# neo.net
KiCad netlist of a schematic drawn in EAGLE
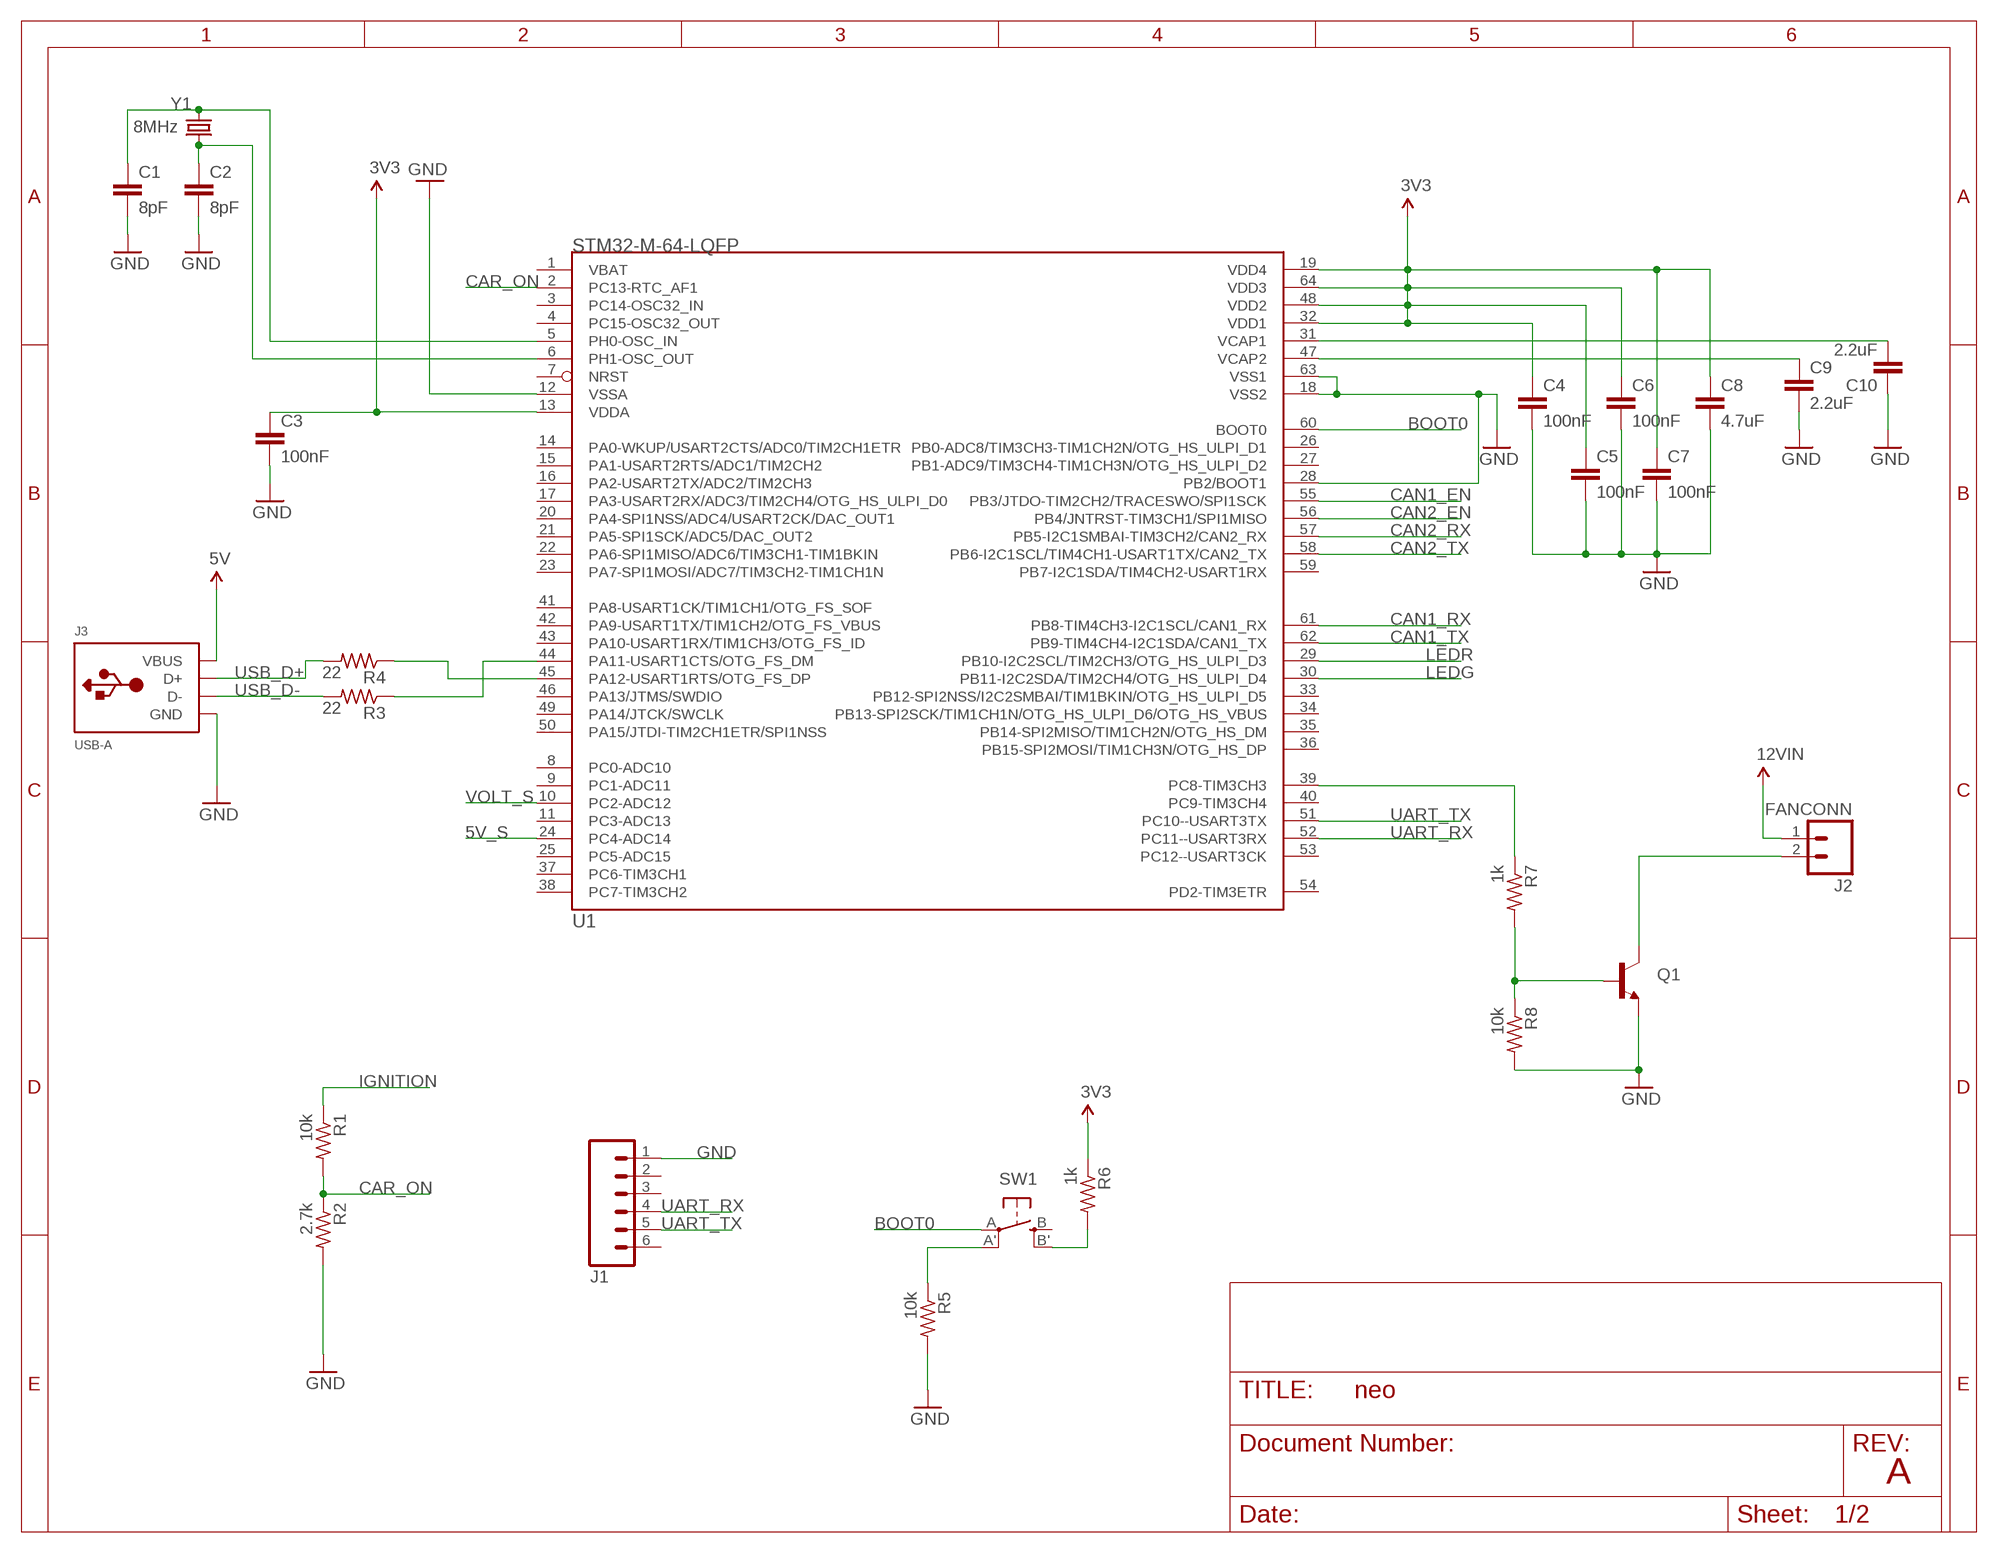
[diagram p0: schematic, sheet 1]
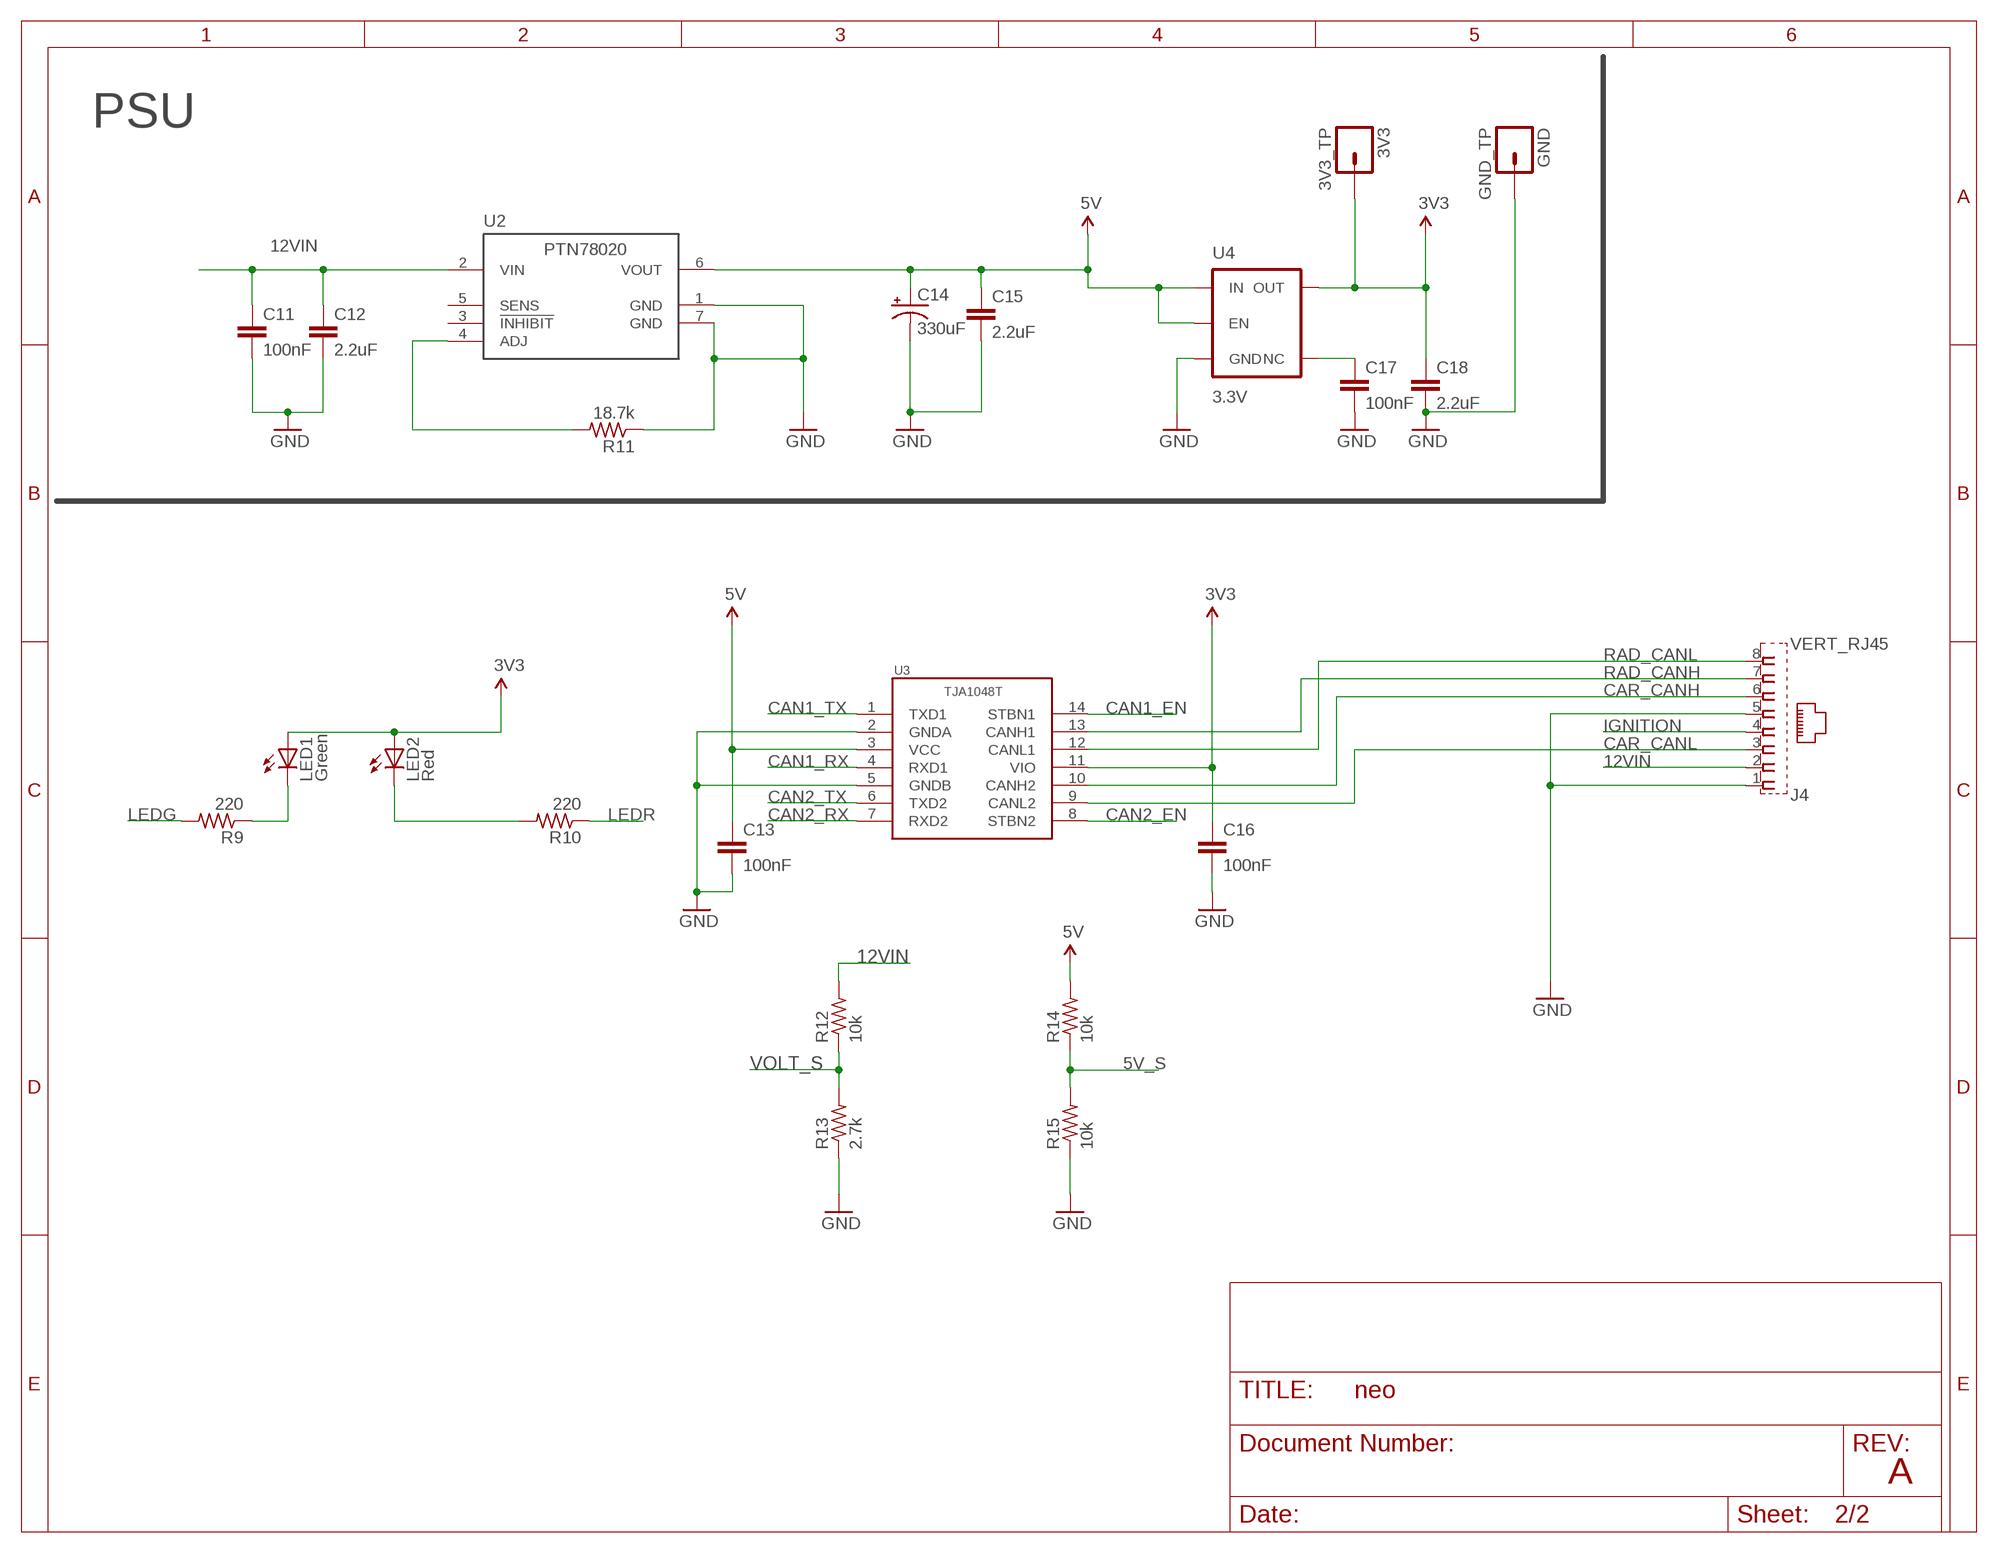
[diagram p1: schematic, sheet 2]

(export (version "E")
  (design (tool "Eeschema 10.0.6"))
  (components
    (comp (ref "C1")
      (value "8pF")
      (footprint "eagle-import:0603-CAP")
      (libsource (lib "eagle-import") (part "1.0UF-16V-10%(0603)"))
    )
    (comp (ref "C2")
      (value "8pF")
      (footprint "eagle-import:0603-CAP")
      (libsource (lib "eagle-import") (part "1.0UF-16V-10%(0603)"))
    )
    (comp (ref "C3")
      (value "100nF")
      (footprint "eagle-import:0603-CAP")
      (libsource (lib "eagle-import") (part "1.0UF-16V-10%(0603)"))
    )
    (comp (ref "C4")
      (value "100nF")
      (footprint "eagle-import:0603-CAP")
      (libsource (lib "eagle-import") (part "1.0UF-16V-10%(0603)"))
    )
    (comp (ref "C5")
      (value "100nF")
      (footprint "eagle-import:0603-CAP")
      (libsource (lib "eagle-import") (part "1.0UF-16V-10%(0603)"))
    )
    (comp (ref "C6")
      (value "100nF")
      (footprint "eagle-import:0603-CAP")
      (libsource (lib "eagle-import") (part "0.1UF-25V-5%(0603)"))
    )
    (comp (ref "C7")
      (value "100nF")
      (footprint "eagle-import:0603-CAP")
      (libsource (lib "eagle-import") (part "1.0UF-16V-10%(0603)"))
    )
    (comp (ref "C8")
      (value "4.7uF")
      (footprint "eagle-import:0603-CAP")
      (libsource (lib "eagle-import") (part "1.0UF-16V-10%(0603)"))
    )
    (comp (ref "C9")
      (value "2.2uF")
      (footprint "eagle-import:0603-CAP")
      (libsource (lib "eagle-import") (part "1.0UF-16V-10%(0603)"))
    )
    (comp (ref "C10")
      (value "2.2uF")
      (footprint "eagle-import:0603-CAP")
      (libsource (lib "eagle-import") (part "1.0UF-16V-10%(0603)"))
    )
    (comp (ref "J1")
      (value "M06NO_SILK_YES_STOP")
      (footprint "eagle-import:1X06_NO_SILK_YES_STOP")
      (libsource (lib "eagle-import") (part "M06NO_SILK_YES_STOP"))
    )
    (comp (ref "J2")
      (value "FANCONN")
      (footprint "eagle-import:1.25CONN")
      (libsource (lib "eagle-import") (part "FANCONN"))
    )
    (comp (ref "J3")
      (value "USB-A")
      (footprint "eagle-import:MOLEX_480371000")
      (libsource (lib "eagle-import") (part "USB-A"))
    )
    (comp (ref "Q1")
      (value "MMBT2222A")
      (footprint "eagle-import:SOT23-3")
      (libsource (lib "eagle-import") (part "TRANSISTOR_NPNMMBT2222A"))
    )
    (comp (ref "R1")
      (value "10k")
      (footprint "eagle-import:R0603")
      (libsource (lib "eagle-import") (part "R-US_R0603"))
    )
    (comp (ref "R2")
      (value "2.7k")
      (footprint "eagle-import:R0603")
      (libsource (lib "eagle-import") (part "R-US_R0603"))
    )
    (comp (ref "R3")
      (value "22")
      (footprint "eagle-import:R0603")
      (libsource (lib "eagle-import") (part "R-US_R0603"))
    )
    (comp (ref "R4")
      (value "22")
      (footprint "eagle-import:R0603")
      (libsource (lib "eagle-import") (part "R-US_R0603"))
    )
    (comp (ref "R5")
      (value "10k")
      (footprint "eagle-import:R0603")
      (libsource (lib "eagle-import") (part "R-US_R0603"))
    )
    (comp (ref "R6")
      (value "1k")
      (footprint "eagle-import:R0603")
      (libsource (lib "eagle-import") (part "R-US_R0603"))
    )
    (comp (ref "R7")
      (value "1k")
      (footprint "eagle-import:R0603")
      (libsource (lib "eagle-import") (part "R-US_R0603"))
    )
    (comp (ref "R8")
      (value "10k")
      (footprint "eagle-import:R0603")
      (libsource (lib "eagle-import") (part "R-US_R0603"))
    )
    (comp (ref "SW1")
      (value "SPST_TACT-EVQQ2")
      (footprint "eagle-import:EVQ-Q2")
      (libsource (lib "eagle-import") (part "SPST_TACT-EVQQ2"))
    )
    (comp (ref "U1")
      (value "STM32-M-64-LQFP")
      (footprint "eagle-import:LQFP64")
      (libsource (lib "eagle-import") (part "STM32-M-64-LQFP"))
    )
    (comp (ref "Y1")
      (value "8MHz")
      (footprint "eagle-import:CRYSTAL-TXC-7A")
      (libsource (lib "eagle-import") (part "CRYSTALTXC-7A"))
    )
    (comp (ref "3V3")
      (value "3V3_TP")
      (footprint "eagle-import:1X01_NO_SILK")
      (libsource (lib "eagle-import") (part "M01PTH_NO_SILK_YES_STOP"))
    )
    (comp (ref "C11")
      (value "100nF")
      (footprint "eagle-import:0603-CAP")
      (libsource (lib "eagle-import") (part "0.22UF-25V-10%(0603)"))
    )
    (comp (ref "C12")
      (value "2.2uF")
      (footprint "eagle-import:0805-CAP")
      (libsource (lib "eagle-import") (part "2.2UF-25V-+80/-20(0805)"))
    )
    (comp (ref "C13")
      (value "100nF")
      (footprint "eagle-import:0603-CAP")
      (libsource (lib "eagle-import") (part "CAP0603-CAP"))
    )
    (comp (ref "C14")
      (value "330uF")
      (footprint "eagle-import:E3,5-8")
      (libsource (lib "eagle-import") (part "C-POL"))
    )
    (comp (ref "C15")
      (value "2.2uF")
      (footprint "eagle-import:0805-CAP")
      (libsource (lib "eagle-import") (part "2.2UF-25V-+80/-20(0805)"))
    )
    (comp (ref "C16")
      (value "100nF")
      (footprint "eagle-import:0603-CAP")
      (libsource (lib "eagle-import") (part "CAP0603-CAP"))
    )
    (comp (ref "C17")
      (value "100nF")
      (footprint "eagle-import:0603-CAP")
      (libsource (lib "eagle-import") (part "CAP0603-CAP"))
    )
    (comp (ref "C18")
      (value "2.2uF")
      (footprint "eagle-import:0603-CAP")
      (libsource (lib "eagle-import") (part "CAP0603-CAP"))
    )
    (comp (ref "GND")
      (value "GND_TP")
      (footprint "eagle-import:1X01_NO_SILK")
      (libsource (lib "eagle-import") (part "M01PTH_NO_SILK_YES_STOP"))
    )
    (comp (ref "J4")
      (value "VERT_RJ45")
      (footprint "eagle-import:GLX-S-88M")
      (libsource (lib "eagle-import") (part "VERT_RJ45"))
    )
    (comp (ref "LED1")
      (value "Green")
      (footprint "eagle-import:CHIPLED_0805")
      (libsource (lib "eagle-import") (part "LEDCHIPLED_0805"))
    )
    (comp (ref "LED2")
      (value "Red")
      (footprint "eagle-import:CHIPLED_0805")
      (libsource (lib "eagle-import") (part "LEDCHIPLED_0805"))
    )
    (comp (ref "R9")
      (value "220")
      (footprint "eagle-import:R0603")
      (libsource (lib "eagle-import") (part "R-US_R0603"))
    )
    (comp (ref "R10")
      (value "220")
      (footprint "eagle-import:R0603")
      (libsource (lib "eagle-import") (part "R-US_R0603"))
    )
    (comp (ref "R11")
      (value "18.7k")
      (footprint "eagle-import:R0603")
      (libsource (lib "eagle-import") (part "R-US_R0603"))
    )
    (comp (ref "R12")
      (value "10k")
      (footprint "eagle-import:R0603")
      (libsource (lib "eagle-import") (part "R-US_R0603"))
    )
    (comp (ref "R13")
      (value "2.7k")
      (footprint "eagle-import:R0603")
      (libsource (lib "eagle-import") (part "R-US_R0603"))
    )
    (comp (ref "R14")
      (value "10k")
      (footprint "eagle-import:R0603")
      (libsource (lib "eagle-import") (part "R-US_R0603"))
    )
    (comp (ref "R15")
      (value "10k")
      (footprint "eagle-import:R0603")
      (libsource (lib "eagle-import") (part "R-US_R0603"))
    )
    (comp (ref "U2")
      (value "PTN78020W")
      (footprint "eagle-import:PTN78020W")
      (libsource (lib "eagle-import") (part "PTN78020W"))
    )
    (comp (ref "U3")
      (value "TJA1048")
      (footprint "eagle-import:SO14")
      (libsource (lib "eagle-import") (part "TJA1048"))
    )
    (comp (ref "U4")
      (value "3.3V")
      (footprint "eagle-import:SOT23-5")
      (libsource (lib "eagle-import") (part "V_REG_AP2112K-3.3V"))
    )
  )
  (nets
    (net (code "1") (name "3V3") (class "Default")
      (node (ref "3V3") (pin "1") (pinfunction "1_1") (pintype "passive"))
      (node (ref "C16") (pin "1") (pinfunction "1_1") (pintype "passive"))
      (node (ref "C18") (pin "1") (pinfunction "1_1") (pintype "passive"))
      (node (ref "C3") (pin "1") (pinfunction "1_1") (pintype "passive"))
      (node (ref "C4") (pin "1") (pinfunction "1_1") (pintype "passive"))
      (node (ref "C5") (pin "1") (pinfunction "1_1") (pintype "passive"))
      (node (ref "C6") (pin "1") (pinfunction "1_1") (pintype "passive"))
      (node (ref "C7") (pin "1") (pinfunction "1_1") (pintype "passive"))
      (node (ref "C8") (pin "1") (pinfunction "1_1") (pintype "passive"))
      (node (ref "LED1") (pin "A") (pinfunction "A_A") (pintype "passive"))
      (node (ref "LED2") (pin "A") (pinfunction "A_A") (pintype "passive"))
      (node (ref "R6") (pin "1") (pinfunction "1_1") (pintype "passive"))
      (node (ref "U1") (pin "13") (pinfunction "VDDA_13") (pintype "power_in"))
      (node (ref "U1") (pin "19") (pinfunction "VDD4_19") (pintype "bidirectional"))
      (node (ref "U1") (pin "32") (pinfunction "VDD1_32") (pintype "power_in"))
      (node (ref "U1") (pin "48") (pinfunction "VDD2_48") (pintype "power_in"))
      (node (ref "U1") (pin "64") (pinfunction "VDD3_64") (pintype "power_in"))
      (node (ref "U3") (pin "11") (pinfunction "VIO_11") (pintype "bidirectional"))
      (node (ref "U4") (pin "5") (pinfunction "OUT_5") (pintype "passive"))
    )
    (net (code "2") (name "5V") (class "Default")
      (node (ref "C13") (pin "1") (pinfunction "1_1") (pintype "passive"))
      (node (ref "C14") (pin "+") (pinfunction "+_+") (pintype "passive"))
      (node (ref "C15") (pin "1") (pinfunction "1_1") (pintype "passive"))
      (node (ref "J3") (pin "1") (pinfunction "VBUS_1") (pintype "power_in"))
      (node (ref "R14") (pin "2") (pinfunction "2_2") (pintype "passive"))
      (node (ref "U2") (pin "6") (pinfunction "VOUT_6") (pintype "bidirectional"))
      (node (ref "U3") (pin "3") (pinfunction "VCC_3") (pintype "power_in"))
      (node (ref "U4") (pin "1") (pinfunction "IN_1") (pintype "input"))
      (node (ref "U4") (pin "3") (pinfunction "EN_3") (pintype "input"))
    )
    (net (code "3") (name "5V_S") (class "Default")
      (node (ref "R14") (pin "1") (pinfunction "1_1") (pintype "passive"))
      (node (ref "R15") (pin "2") (pinfunction "2_2") (pintype "passive"))
      (node (ref "U1") (pin "24") (pinfunction "PC4-ADC14_24") (pintype "bidirectional"))
    )
    (net (code "4") (name "12VIN") (class "Default")
      (node (ref "C11") (pin "1") (pinfunction "1_1") (pintype "passive"))
      (node (ref "C12") (pin "1") (pinfunction "1_1") (pintype "passive"))
      (node (ref "J2") (pin "1") (pinfunction "1_1") (pintype "passive"))
      (node (ref "J4") (pin "2") (pinfunction "2_2") (pintype "passive"))
      (node (ref "R12") (pin "2") (pinfunction "2_2") (pintype "passive"))
      (node (ref "U2") (pin "2") (pinfunction "VIN_2") (pintype "bidirectional"))
    )
    (net (code "5") (name "BOOT0") (class "Default")
      (node (ref "SW1") (pin "A") (pinfunction "P_A") (pintype "passive"))
      (node (ref "U1") (pin "60") (pinfunction "BOOT0_60") (pintype "input"))
    )
    (net (code "6") (name "CAN1_EN") (class "Default")
      (node (ref "U1") (pin "55") (pinfunction "PB3/JTDO-TIM2CH2/TRACESWO/SPI1SCK_55") (pintype "bidirectional"))
      (node (ref "U3") (pin "14") (pinfunction "STBN1_14") (pintype "bidirectional"))
    )
    (net (code "7") (name "CAN1_RX") (class "Default")
      (node (ref "U1") (pin "61") (pinfunction "PB8-TIM4CH3-I2C1SCL/CAN1_RX_61") (pintype "bidirectional"))
      (node (ref "U3") (pin "4") (pinfunction "RXD1_4") (pintype "bidirectional"))
    )
    (net (code "8") (name "CAN1_TX") (class "Default")
      (node (ref "U1") (pin "62") (pinfunction "PB9-TIM4CH4-I2C1SDA/CAN1_TX_62") (pintype "bidirectional"))
      (node (ref "U3") (pin "1") (pinfunction "TXD1_1") (pintype "bidirectional"))
    )
    (net (code "9") (name "CAN2_EN") (class "Default")
      (node (ref "U1") (pin "56") (pinfunction "PB4/JNTRST-TIM3CH1/SPI1MISO_56") (pintype "bidirectional"))
      (node (ref "U3") (pin "8") (pinfunction "STBN2_8") (pintype "bidirectional"))
    )
    (net (code "10") (name "CAN2_RX") (class "Default")
      (node (ref "U1") (pin "57") (pinfunction "PB5-I2C1SMBAI-TIM3CH2/CAN2_RX_57") (pintype "bidirectional"))
      (node (ref "U3") (pin "7") (pinfunction "RXD2_7") (pintype "bidirectional"))
    )
    (net (code "11") (name "CAN2_TX") (class "Default")
      (node (ref "U1") (pin "58") (pinfunction "PB6-I2C1SCL/TIM4CH1-USART1TX/CAN2_TX_58") (pintype "bidirectional"))
      (node (ref "U3") (pin "6") (pinfunction "TXD2_6") (pintype "bidirectional"))
    )
    (net (code "12") (name "CAR_CANH") (class "Default")
      (node (ref "J4") (pin "6") (pinfunction "6_6") (pintype "passive"))
      (node (ref "U3") (pin "10") (pinfunction "CANH2_10") (pintype "bidirectional"))
    )
    (net (code "13") (name "CAR_CANL") (class "Default")
      (node (ref "J4") (pin "3") (pinfunction "3_3") (pintype "passive"))
      (node (ref "U3") (pin "9") (pinfunction "CANL2_9") (pintype "bidirectional"))
    )
    (net (code "14") (name "CAR_ON") (class "Default")
      (node (ref "R1") (pin "2") (pinfunction "2_2") (pintype "passive"))
      (node (ref "R2") (pin "1") (pinfunction "1_1") (pintype "passive"))
      (node (ref "U1") (pin "2") (pinfunction "PC13-RTC_AF1_2") (pintype "bidirectional"))
    )
    (net (code "15") (name "GND") (class "Default")
      (node (ref "C1") (pin "2") (pinfunction "2_2") (pintype "passive"))
      (node (ref "C10") (pin "1") (pinfunction "1_1") (pintype "passive"))
      (node (ref "C11") (pin "2") (pinfunction "2_2") (pintype "passive"))
      (node (ref "C12") (pin "2") (pinfunction "2_2") (pintype "passive"))
      (node (ref "C13") (pin "2") (pinfunction "2_2") (pintype "passive"))
      (node (ref "C14") (pin "-") (pinfunction "-_-") (pintype "passive"))
      (node (ref "C15") (pin "2") (pinfunction "2_2") (pintype "passive"))
      (node (ref "C16") (pin "2") (pinfunction "2_2") (pintype "passive"))
      (node (ref "C17") (pin "2") (pinfunction "2_2") (pintype "passive"))
      (node (ref "C18") (pin "2") (pinfunction "2_2") (pintype "passive"))
      (node (ref "C2") (pin "2") (pinfunction "2_2") (pintype "passive"))
      (node (ref "C3") (pin "2") (pinfunction "2_2") (pintype "passive"))
      (node (ref "C4") (pin "2") (pinfunction "2_2") (pintype "passive"))
      (node (ref "C5") (pin "2") (pinfunction "2_2") (pintype "passive"))
      (node (ref "C6") (pin "2") (pinfunction "2_2") (pintype "passive"))
      (node (ref "C7") (pin "2") (pinfunction "2_2") (pintype "passive"))
      (node (ref "C8") (pin "2") (pinfunction "2_2") (pintype "passive"))
      (node (ref "C9") (pin "2") (pinfunction "2_2") (pintype "passive"))
      (node (ref "GND") (pin "1") (pinfunction "1_1") (pintype "passive"))
      (node (ref "J1") (pin "1") (pinfunction "1_1") (pintype "passive"))
      (node (ref "J3") (pin "4") (pinfunction "GND_4") (pintype "power_in"))
      (node (ref "J4") (pin "1") (pinfunction "1_1") (pintype "passive"))
      (node (ref "J4") (pin "5") (pinfunction "5_5") (pintype "passive"))
      (node (ref "Q1") (pin "2") (pinfunction "E_2") (pintype "passive"))
      (node (ref "R11") (pin "1") (pinfunction "1_1") (pintype "passive"))
      (node (ref "R13") (pin "1") (pinfunction "1_1") (pintype "passive"))
      (node (ref "R15") (pin "1") (pinfunction "1_1") (pintype "passive"))
      (node (ref "R2") (pin "2") (pinfunction "2_2") (pintype "passive"))
      (node (ref "R5") (pin "2") (pinfunction "2_2") (pintype "passive"))
      (node (ref "R8") (pin "2") (pinfunction "2_2") (pintype "passive"))
      (node (ref "U1") (pin "12") (pinfunction "VSSA_12") (pintype "power_in"))
      (node (ref "U1") (pin "18") (pinfunction "VSS2_18") (pintype "bidirectional"))
      (node (ref "U1") (pin "28") (pinfunction "PB2/BOOT1_28") (pintype "bidirectional"))
      (node (ref "U1") (pin "63") (pinfunction "VSS1_63") (pintype "power_in"))
      (node (ref "U2") (pin "1") (pinfunction "GND_1") (pintype "bidirectional"))
      (node (ref "U2") (pin "7") (pinfunction "GND_7") (pintype "bidirectional"))
      (node (ref "U3") (pin "2") (pinfunction "GNDA_2") (pintype "bidirectional"))
      (node (ref "U3") (pin "5") (pinfunction "GNDB_5") (pintype "bidirectional"))
      (node (ref "U4") (pin "2") (pinfunction "GND_2") (pintype "input"))
    )
    (net (code "16") (name "IGNITION") (class "Default")
      (node (ref "J4") (pin "4") (pinfunction "4_4") (pintype "passive"))
      (node (ref "R1") (pin "1") (pinfunction "1_1") (pintype "passive"))
    )
    (net (code "17") (name "LEDG") (class "Default")
      (node (ref "R9") (pin "2") (pinfunction "2_2") (pintype "passive"))
      (node (ref "U1") (pin "30") (pinfunction "PB11-I2C2SDA/TIM2CH4/OTG_HS_ULPI_D4_30") (pintype "bidirectional"))
    )
    (net (code "18") (name "LEDR") (class "Default")
      (node (ref "R10") (pin "1") (pinfunction "1_1") (pintype "passive"))
      (node (ref "U1") (pin "29") (pinfunction "PB10-I2C2SCL/TIM2CH3/OTG_HS_ULPI_D3_29") (pintype "bidirectional"))
    )
    (net (code "19") (name "Net-(LED1-PadC)") (class "Default")
      (node (ref "LED1") (pin "C") (pinfunction "C_C") (pintype "passive"))
      (node (ref "R9") (pin "1") (pinfunction "1_1") (pintype "passive"))
    )
    (net (code "20") (name "Net-(LED2-PadC)") (class "Default")
      (node (ref "LED2") (pin "C") (pinfunction "C_C") (pintype "passive"))
      (node (ref "R10") (pin "2") (pinfunction "2_2") (pintype "passive"))
    )
    (net (code "21") (name "Net-(Q1-B)") (class "Default")
      (node (ref "Q1") (pin "1") (pinfunction "B_1") (pintype "passive"))
      (node (ref "R7") (pin "2") (pinfunction "2_2") (pintype "passive"))
      (node (ref "R8") (pin "1") (pinfunction "1_1") (pintype "passive"))
    )
    (net (code "22") (name "Net-(Q1-C)") (class "Default")
      (node (ref "J2") (pin "2") (pinfunction "2_2") (pintype "passive"))
      (node (ref "Q1") (pin "3") (pinfunction "C_3") (pintype "passive"))
    )
    (net (code "23") (name "Net-(SW1-P1)") (class "Default")
      (node (ref "R5") (pin "1") (pinfunction "1_1") (pintype "passive"))
      (node (ref "SW1") (pin "A'") (pinfunction "P1_A'") (pintype "passive"))
    )
    (net (code "24") (name "Net-(SW1-S1)") (class "Default")
      (node (ref "R6") (pin "2") (pinfunction "2_2") (pintype "passive"))
      (node (ref "SW1") (pin "B'") (pinfunction "S1_B'") (pintype "passive"))
    )
    (net (code "25") (name "Net-(U1-PA11-USART1CTS{slash}OTG_FS_DM)") (class "Default")
      (node (ref "R3") (pin "1") (pinfunction "1_1") (pintype "passive"))
      (node (ref "U1") (pin "44") (pinfunction "PA11-USART1CTS/OTG_FS_DM_44") (pintype "bidirectional"))
    )
    (net (code "26") (name "Net-(U1-PA12-USART1RTS{slash}OTG_FS_DP)") (class "Default")
      (node (ref "R4") (pin "1") (pinfunction "1_1") (pintype "passive"))
      (node (ref "U1") (pin "45") (pinfunction "PA12-USART1RTS/OTG_FS_DP_45") (pintype "bidirectional"))
    )
    (net (code "27") (name "Net-(U1-PC8-TIM3CH3)") (class "Default")
      (node (ref "R7") (pin "1") (pinfunction "1_1") (pintype "passive"))
      (node (ref "U1") (pin "39") (pinfunction "PC8-TIM3CH3_39") (pintype "bidirectional"))
    )
    (net (code "28") (name "Net-(U1-PH0-OSC_IN)") (class "Default")
      (node (ref "C1") (pin "1") (pinfunction "1_1") (pintype "passive"))
      (node (ref "U1") (pin "5") (pinfunction "PH0-OSC_IN_5") (pintype "input"))
      (node (ref "Y1") (pin "P$1") (pinfunction "1_P$1") (pintype "passive"))
    )
    (net (code "29") (name "Net-(U1-PH1-OSC_OUT)") (class "Default")
      (node (ref "C2") (pin "1") (pinfunction "1_1") (pintype "passive"))
      (node (ref "U1") (pin "6") (pinfunction "PH1-OSC_OUT_6") (pintype "output"))
      (node (ref "Y1") (pin "P$2") (pinfunction "2_P$2") (pintype "passive"))
    )
    (net (code "30") (name "Net-(U1-VCAP1)") (class "Default")
      (node (ref "C10") (pin "2") (pinfunction "2_2") (pintype "passive"))
      (node (ref "U1") (pin "31") (pinfunction "VCAP1_31") (pintype "power_in"))
    )
    (net (code "31") (name "Net-(U1-VCAP2)") (class "Default")
      (node (ref "C9") (pin "1") (pinfunction "1_1") (pintype "passive"))
      (node (ref "U1") (pin "47") (pinfunction "VCAP2_47") (pintype "power_in"))
    )
    (net (code "32") (name "Net-(U2-ADJ)") (class "Default")
      (node (ref "R11") (pin "2") (pinfunction "2_2") (pintype "passive"))
      (node (ref "U2") (pin "4") (pinfunction "ADJ_4") (pintype "bidirectional"))
    )
    (net (code "33") (name "Net-(U4-NC)") (class "Default")
      (node (ref "C17") (pin "1") (pinfunction "1_1") (pintype "passive"))
      (node (ref "U4") (pin "4") (pinfunction "NC_4") (pintype "input"))
    )
    (net (code "34") (name "RAD_CANH") (class "Default")
      (node (ref "J4") (pin "7") (pinfunction "7_7") (pintype "passive"))
      (node (ref "U3") (pin "13") (pinfunction "CANH1_13") (pintype "bidirectional"))
    )
    (net (code "35") (name "RAD_CANL") (class "Default")
      (node (ref "J4") (pin "8") (pinfunction "8_8") (pintype "passive"))
      (node (ref "U3") (pin "12") (pinfunction "CANL1_12") (pintype "bidirectional"))
    )
    (net (code "36") (name "UART_RX") (class "Default")
      (node (ref "J1") (pin "4") (pinfunction "4_4") (pintype "passive"))
      (node (ref "U1") (pin "52") (pinfunction "PC11--USART3RX_52") (pintype "bidirectional"))
    )
    (net (code "37") (name "UART_TX") (class "Default")
      (node (ref "J1") (pin "5") (pinfunction "5_5") (pintype "passive"))
      (node (ref "U1") (pin "51") (pinfunction "PC10--USART3TX_51") (pintype "bidirectional"))
    )
    (net (code "38") (name "USB_D+") (class "Default")
      (node (ref "J3") (pin "3") (pinfunction "D+_3") (pintype "bidirectional"))
      (node (ref "R4") (pin "2") (pinfunction "2_2") (pintype "passive"))
    )
    (net (code "39") (name "USB_D-") (class "Default")
      (node (ref "J3") (pin "2") (pinfunction "D-_2") (pintype "bidirectional"))
      (node (ref "R3") (pin "2") (pinfunction "2_2") (pintype "passive"))
    )
    (net (code "40") (name "VBAT") (class "Default")
      (node (ref "U1") (pin "1") (pinfunction "VBAT_1") (pintype "power_in"))
    )
    (net (code "41") (name "VOLT_S") (class "Default")
      (node (ref "R12") (pin "1") (pinfunction "1_1") (pintype "passive"))
      (node (ref "R13") (pin "2") (pinfunction "2_2") (pintype "passive"))
      (node (ref "U1") (pin "10") (pinfunction "PC2-ADC12_10") (pintype "bidirectional"))
    )
    (net (code "42") (name "unconnected-(J1-Pad2)") (class "Default")
      (node (ref "J1") (pin "2") (pinfunction "2_2") (pintype "passive"))
    )
    (net (code "43") (name "unconnected-(J1-Pad3)") (class "Default")
      (node (ref "J1") (pin "3") (pinfunction "3_3") (pintype "passive"))
    )
    (net (code "44") (name "unconnected-(J1-Pad6)") (class "Default")
      (node (ref "J1") (pin "6") (pinfunction "6_6") (pintype "passive"))
    )
    (net (code "45") (name "unconnected-(SW1-S-PadB)") (class "Default")
      (node (ref "SW1") (pin "B") (pinfunction "S_B") (pintype "passive"))
    )
    (net (code "46") (name "unconnected-(U1-NRST-Pad7)") (class "Default")
      (node (ref "U1") (pin "7") (pinfunction "NRST_7") (pintype "bidirectional"))
    )
    (net (code "47") (name "unconnected-(U1-PA0-WKUP{slash}USART2CTS{slash}ADC0{slash}TIM2CH1ETR-Pad14)") (class "Default")
      (node (ref "U1") (pin "14") (pinfunction "PA0-WKUP/USART2CTS/ADC0/TIM2CH1ETR_14") (pintype "bidirectional"))
    )
    (net (code "48") (name "unconnected-(U1-PA1-USART2RTS{slash}ADC1{slash}TIM2CH2-Pad15)") (class "Default")
      (node (ref "U1") (pin "15") (pinfunction "PA1-USART2RTS/ADC1/TIM2CH2_15") (pintype "bidirectional"))
    )
    (net (code "49") (name "unconnected-(U1-PA2-USART2TX{slash}ADC2{slash}TIM2CH3-Pad16)") (class "Default")
      (node (ref "U1") (pin "16") (pinfunction "PA2-USART2TX/ADC2/TIM2CH3_16") (pintype "bidirectional"))
    )
    (net (code "50") (name "unconnected-(U1-PA3-USART2RX{slash}ADC3{slash}TIM2CH4{slash}OTG_HS_ULPI_D0-Pad17)") (class "Default")
      (node (ref "U1") (pin "17") (pinfunction "PA3-USART2RX/ADC3/TIM2CH4/OTG_HS_ULPI_D0_17") (pintype "bidirectional"))
    )
    (net (code "51") (name "unconnected-(U1-PA4-SPI1NSS{slash}ADC4{slash}USART2CK{slash}DAC_OUT1-Pad20)") (class "Default")
      (node (ref "U1") (pin "20") (pinfunction "PA4-SPI1NSS/ADC4/USART2CK/DAC_OUT1_20") (pintype "bidirectional"))
    )
    (net (code "52") (name "unconnected-(U1-PA5-SPI1SCK{slash}ADC5{slash}DAC_OUT2-Pad21)") (class "Default")
      (node (ref "U1") (pin "21") (pinfunction "PA5-SPI1SCK/ADC5/DAC_OUT2_21") (pintype "bidirectional"))
    )
    (net (code "53") (name "unconnected-(U1-PA6-SPI1MISO{slash}ADC6{slash}TIM3CH1-TIM1BKIN-Pad22)") (class "Default")
      (node (ref "U1") (pin "22") (pinfunction "PA6-SPI1MISO/ADC6/TIM3CH1-TIM1BKIN_22") (pintype "bidirectional"))
    )
    (net (code "54") (name "unconnected-(U1-PA7-SPI1MOSI{slash}ADC7{slash}TIM3CH2-TIM1CH1N-Pad23)") (class "Default")
      (node (ref "U1") (pin "23") (pinfunction "PA7-SPI1MOSI/ADC7/TIM3CH2-TIM1CH1N_23") (pintype "bidirectional"))
    )
    (net (code "55") (name "unconnected-(U1-PA8-USART1CK{slash}TIM1CH1{slash}OTG_FS_SOF-Pad41)") (class "Default")
      (node (ref "U1") (pin "41") (pinfunction "PA8-USART1CK/TIM1CH1/OTG_FS_SOF_41") (pintype "bidirectional"))
    )
    (net (code "56") (name "unconnected-(U1-PA9-USART1TX{slash}TIM1CH2{slash}OTG_FS_VBUS-Pad42)") (class "Default")
      (node (ref "U1") (pin "42") (pinfunction "PA9-USART1TX/TIM1CH2/OTG_FS_VBUS_42") (pintype "bidirectional"))
    )
    (net (code "57") (name "unconnected-(U1-PA10-USART1RX{slash}TIM1CH3{slash}OTG_FS_ID-Pad43)") (class "Default")
      (node (ref "U1") (pin "43") (pinfunction "PA10-USART1RX/TIM1CH3/OTG_FS_ID_43") (pintype "bidirectional"))
    )
    (net (code "58") (name "unconnected-(U1-PA13{slash}JTMS{slash}SWDIO-Pad46)") (class "Default")
      (node (ref "U1") (pin "46") (pinfunction "PA13/JTMS/SWDIO_46") (pintype "bidirectional"))
    )
    (net (code "59") (name "unconnected-(U1-PA14{slash}JTCK{slash}SWCLK-Pad49)") (class "Default")
      (node (ref "U1") (pin "49") (pinfunction "PA14/JTCK/SWCLK_49") (pintype "bidirectional"))
    )
    (net (code "60") (name "unconnected-(U1-PA15{slash}JTDI-TIM2CH1ETR{slash}SPI1NSS-Pad50)") (class "Default")
      (node (ref "U1") (pin "50") (pinfunction "PA15/JTDI-TIM2CH1ETR/SPI1NSS_50") (pintype "bidirectional"))
    )
    (net (code "61") (name "unconnected-(U1-PB0-ADC8{slash}TIM3CH3-TIM1CH2N{slash}OTG_HS_ULPI_D1-Pad26)") (class "Default")
      (node (ref "U1") (pin "26") (pinfunction "PB0-ADC8/TIM3CH3-TIM1CH2N/OTG_HS_ULPI_D1_26") (pintype "bidirectional"))
    )
    (net (code "62") (name "unconnected-(U1-PB1-ADC9{slash}TIM3CH4-TIM1CH3N{slash}OTG_HS_ULPI_D2-Pad27)") (class "Default")
      (node (ref "U1") (pin "27") (pinfunction "PB1-ADC9/TIM3CH4-TIM1CH3N/OTG_HS_ULPI_D2_27") (pintype "bidirectional"))
    )
    (net (code "63") (name "unconnected-(U1-PB7-I2C1SDA{slash}TIM4CH2-USART1RX-Pad59)") (class "Default")
      (node (ref "U1") (pin "59") (pinfunction "PB7-I2C1SDA/TIM4CH2-USART1RX_59") (pintype "bidirectional"))
    )
    (net (code "64") (name "unconnected-(U1-PB12-SPI2NSS{slash}I2C2SMBAI{slash}TIM1BKIN{slash}OTG_HS_ULPI_D5-Pad33)") (class "Default")
      (node (ref "U1") (pin "33") (pinfunction "PB12-SPI2NSS/I2C2SMBAI/TIM1BKIN/OTG_HS_ULPI_D5_33") (pintype "bidirectional"))
    )
    (net (code "65") (name "unconnected-(U1-PB13-SPI2SCK{slash}TIM1CH1N{slash}OTG_HS_ULPI_D6{slash}OTG_HS_VBUS-Pad34)") (class "Default")
      (node (ref "U1") (pin "34") (pinfunction "PB13-SPI2SCK/TIM1CH1N/OTG_HS_ULPI_D6/OTG_HS_VBUS_34") (pintype "bidirectional"))
    )
    (net (code "66") (name "unconnected-(U1-PB14-SPI2MISO{slash}TIM1CH2N{slash}OTG_HS_DM-Pad35)") (class "Default")
      (node (ref "U1") (pin "35") (pinfunction "PB14-SPI2MISO/TIM1CH2N/OTG_HS_DM_35") (pintype "bidirectional"))
    )
    (net (code "67") (name "unconnected-(U1-PB15-SPI2MOSI{slash}TIM1CH3N{slash}OTG_HS_DP-Pad36)") (class "Default")
      (node (ref "U1") (pin "36") (pinfunction "PB15-SPI2MOSI/TIM1CH3N/OTG_HS_DP_36") (pintype "bidirectional"))
    )
    (net (code "68") (name "unconnected-(U1-PC0-ADC10-Pad8)") (class "Default")
      (node (ref "U1") (pin "8") (pinfunction "PC0-ADC10_8") (pintype "bidirectional"))
    )
    (net (code "69") (name "unconnected-(U1-PC1-ADC11-Pad9)") (class "Default")
      (node (ref "U1") (pin "9") (pinfunction "PC1-ADC11_9") (pintype "bidirectional"))
    )
    (net (code "70") (name "unconnected-(U1-PC3-ADC13-Pad11)") (class "Default")
      (node (ref "U1") (pin "11") (pinfunction "PC3-ADC13_11") (pintype "bidirectional"))
    )
    (net (code "71") (name "unconnected-(U1-PC5-ADC15-Pad25)") (class "Default")
      (node (ref "U1") (pin "25") (pinfunction "PC5-ADC15_25") (pintype "bidirectional"))
    )
    (net (code "72") (name "unconnected-(U1-PC6-TIM3CH1-Pad37)") (class "Default")
      (node (ref "U1") (pin "37") (pinfunction "PC6-TIM3CH1_37") (pintype "bidirectional"))
    )
    (net (code "73") (name "unconnected-(U1-PC7-TIM3CH2-Pad38)") (class "Default")
      (node (ref "U1") (pin "38") (pinfunction "PC7-TIM3CH2_38") (pintype "bidirectional"))
    )
    (net (code "74") (name "unconnected-(U1-PC9-TIM3CH4-Pad40)") (class "Default")
      (node (ref "U1") (pin "40") (pinfunction "PC9-TIM3CH4_40") (pintype "bidirectional"))
    )
    (net (code "75") (name "unconnected-(U1-PC12--USART3CK-Pad53)") (class "Default")
      (node (ref "U1") (pin "53") (pinfunction "PC12--USART3CK_53") (pintype "bidirectional"))
    )
    (net (code "76") (name "unconnected-(U1-PC14-OSC32_IN-Pad3)") (class "Default")
      (node (ref "U1") (pin "3") (pinfunction "PC14-OSC32_IN_3") (pintype "bidirectional"))
    )
    (net (code "77") (name "unconnected-(U1-PC15-OSC32_OUT-Pad4)") (class "Default")
      (node (ref "U1") (pin "4") (pinfunction "PC15-OSC32_OUT_4") (pintype "bidirectional"))
    )
    (net (code "78") (name "unconnected-(U1-PD2-TIM3ETR-Pad54)") (class "Default")
      (node (ref "U1") (pin "54") (pinfunction "PD2-TIM3ETR_54") (pintype "bidirectional"))
    )
    (net (code "79") (name "unconnected-(U2-SENS-Pad5)") (class "Default")
      (node (ref "U2") (pin "5") (pinfunction "SENS_5") (pintype "bidirectional"))
    )
    (net (code "80") (name "unconnected-(U2-~{INHIBIT}-Pad3)") (class "Default")
      (node (ref "U2") (pin "3") (pinfunction "~{INHIBIT}_3") (pintype "bidirectional"))
    )
  )
)
